# leo_RPI_BUCK.net
KiCad netlist of a schematic drawn in Altium Designer
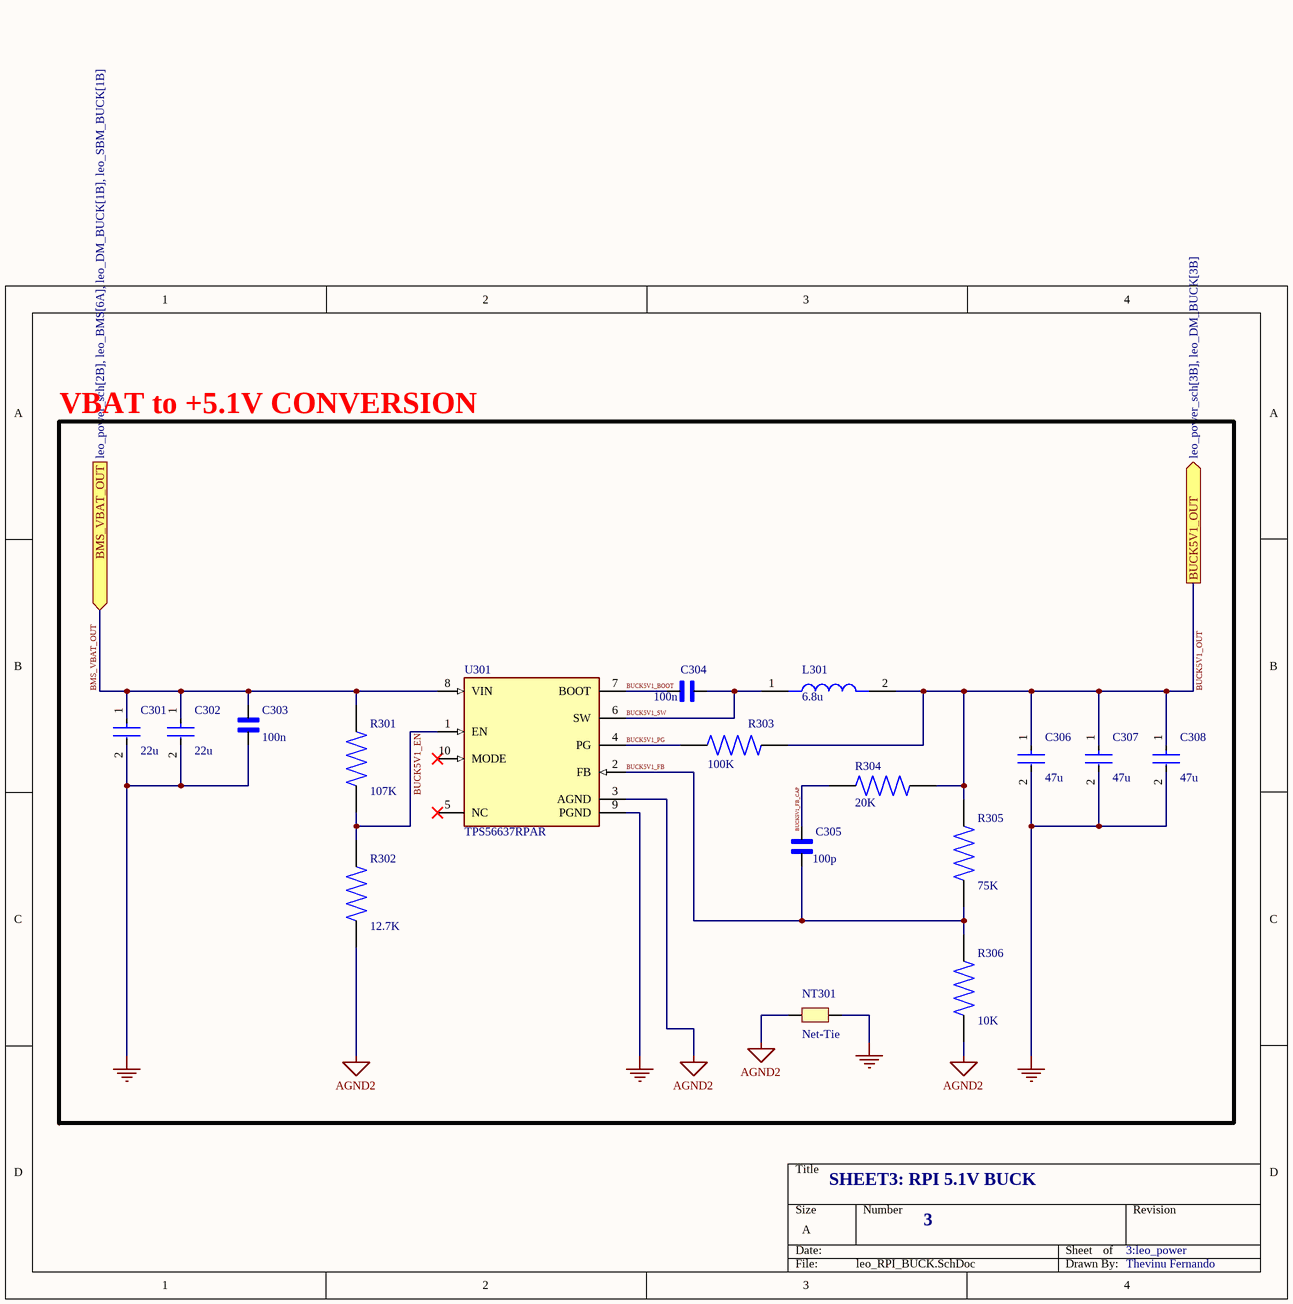
[diagram p0: leo_RPI_BUCK.SchDoc]

(export (version "E")
  (design (tool "Eeschema 10.0.6"))
  (components
    (comp (ref "C301")
      (value "22u")
      (footprint "CAP_1206")
      (fields
        (field (name "MOUSER PART NUMBER") "187-CL31A226KAHNNNE")
        (field (name "PART NUMBER") "CL31A226KAHNNNE")
        (field (name "DIGIKEY PART NUMBER") "1276-3047-1-ND")
      )
      (libsource (lib "leo_power_schlib") (part "CAP_1206"))
    )
    (comp (ref "C302")
      (value "22u")
      (footprint "CAP_1206")
      (fields
        (field (name "MOUSER PART NUMBER") "187-CL31A226KAHNNNE")
        (field (name "PART NUMBER") "CL31A226KAHNNNE")
        (field (name "DIGIKEY PART NUMBER") "1276-3047-1-ND")
      )
      (libsource (lib "leo_power_schlib") (part "CAP_1206"))
    )
    (comp (ref "C303")
      (value "100n")
      (footprint "CAP_0603")
      (description "Â±10% 50V Ceramic Capacitor X7R 0603 (1608 Metric)")
      (fields (field (name "MF") "Samsung Electro-Mechanics") (field (name "MP") "CL10B104KB8NNNC"))
      (libsource (lib "leo_power_schlib") (part "CAP_0603"))
    )
    (comp (ref "C304")
      (value "100n")
      (footprint "CAP_0402")
      (description "±10% 50V Ceramic Capacitor X7R 0402")
      (fields (field (name "MF") "Samsung") (field (name "MP") "CL05B104KO5NNNC"))
      (libsource (lib "leo_power_schlib") (part "CAP_0402"))
    )
    (comp (ref "C305")
      (value "100p")
      (footprint "CAP_0402")
      (description "±10% 50V Ceramic Capacitor X7R 0402")
      (fields (field (name "MF") "Samsung") (field (name "MP") "CL05B104KO5NNNC"))
      (libsource (lib "") (part "CAP_0402_1"))
    )
    (comp (ref "C306")
      (value "47u")
      (footprint "CAP_1206")
      (fields
        (field (name "MOUSER PART NUMBER") "187-CL31A226KAHNNNE")
        (field (name "PART NUMBER") "CL31A226KAHNNNE")
        (field (name "DIGIKEY PART NUMBER") "1276-3047-1-ND")
      )
      (libsource (lib "leo_power_schlib") (part "CAP_1206"))
    )
    (comp (ref "C307")
      (value "47u")
      (footprint "CAP_1206")
      (fields
        (field (name "MOUSER PART NUMBER") "187-CL31A226KAHNNNE")
        (field (name "PART NUMBER") "CL31A226KAHNNNE")
        (field (name "DIGIKEY PART NUMBER") "1276-3047-1-ND")
      )
      (libsource (lib "leo_power_schlib") (part "CAP_1206"))
    )
    (comp (ref "C308")
      (value "47u")
      (footprint "CAP_1206")
      (fields
        (field (name "MOUSER PART NUMBER") "187-CL31A226KAHNNNE")
        (field (name "PART NUMBER") "CL31A226KAHNNNE")
        (field (name "DIGIKEY PART NUMBER") "1276-3047-1-ND")
      )
      (libsource (lib "leo_power_schlib") (part "CAP_1206"))
    )
    (comp (ref "L301")
      (value "6.8u")
      (footprint "IND_104CDMCCDS-8R2MC")
      (description "Inductor Power Shielded/Molded Wirewound 8.2uH 20% 100KHz Metal 8.3A 0.027Ohm DCR 4040 T/R")
      (fields (field (name "MF") "Sumida") (field (name "MP") "104CDMCCDS-8R2MC"))
      (libsource (lib "leo_power_schlib") (part "104CDMCCDS-8R2MC"))
    )
    (comp (ref "NT301")
      (value "Net-Tie")
      (footprint "NET-TIE_SMD")
      (description "Single point connection between nets.")
      (libsource (lib "leo_power_schlib") (part "NET-TIE"))
    )
    (comp (ref "R301")
      (value "107K")
      (footprint "RES_0603")
      (description "Â±1% 0.1W, 1/10W Chip Resistor 0603 (1608 Metric) Moisture Resistant Thick Film")
      (fields (field (name "MF") "Yageo") (field (name "MP") "RC0603FR-0791KL"))
      (libsource (lib "leo_power_schlib") (part "RES_0603"))
    )
    (comp (ref "R302")
      (value "12.7K")
      (footprint "RES_0603")
      (description "Â±1% 0.1W, 1/10W Chip Resistor 0603 (1608 Metric) Moisture Resistant Thick Film")
      (fields (field (name "MF") "Yageo") (field (name "MP") "RC0603FR-0791KL"))
      (libsource (lib "leo_power_schlib") (part "RES_0603"))
    )
    (comp (ref "R303")
      (value "100K")
      (footprint "RES_0402")
      (description "Chip Resistor 0402 (1005 Metric) Automotive AEC-Q200 Thick Film")
      (fields (field (name "MF") "Panasonic") (field (name "MP") "ERJ-2RKF1002X"))
      (libsource (lib "leo_power_schlib") (part "RES_0402"))
    )
    (comp (ref "R304")
      (value "20K")
      (footprint "RES_0402")
      (description "Chip Resistor 0402 (1005 Metric) Automotive AEC-Q200 Thick Film")
      (fields (field (name "MF") "Panasonic") (field (name "MP") "ERJ-2RKF1002X"))
      (libsource (lib "leo_power_schlib") (part "RES_0402"))
    )
    (comp (ref "R305")
      (value "75K")
      (footprint "RES_0603")
      (description "Â±1% 0.1W, 1/10W Chip Resistor 0603 (1608 Metric) Moisture Resistant Thick Film")
      (fields (field (name "MF") "Yageo") (field (name "MP") "RC0603FR-0791KL"))
      (libsource (lib "leo_power_schlib") (part "RES_0603"))
    )
    (comp (ref "R306")
      (value "10K")
      (footprint "RES_0603")
      (description "Â±1% 0.1W, 1/10W Chip Resistor 0603 (1608 Metric) Moisture Resistant Thick Film")
      (fields (field (name "MF") "Yageo") (field (name "MP") "RC0603FR-0791KL"))
      (libsource (lib "leo_power_schlib") (part "RES_0603"))
    )
    (comp (ref "U301")
      (value "TPS56637RPAR")
      (footprint "FP-RPA0010A-MFG")
      (description "Buck Switching Regulator IC Adjustable 0.6V~13V 1 Output 6A VQFN-10-HR(3x3)")
      (fields
        (field (name "OCTOPART") "https://octopart.com/tps56637rpar-texas+instruments-97650653")
        (field (name "MANUFACTURER") "Texas Instruments")
      )
      (libsource (lib "leo_power_schlib") (part "TPS56637RPAR"))
    )
  )
  (nets
    (net (code "1") (name "/BMS_VBAT_OUT") (class "Default")
      (node (ref "C301") (pin "1") (pinfunction "1_1") (pintype "passive"))
      (node (ref "C302") (pin "1") (pinfunction "1_1") (pintype "passive"))
      (node (ref "C303") (pin "2") (pinfunction "2_2") (pintype "passive"))
      (node (ref "R301") (pin "2") (pinfunction "2_2") (pintype "passive"))
      (node (ref "U301") (pin "8") (pinfunction "VIN_8") (pintype "input"))
    )
    (net (code "2") (name "/BUCK5V1_BOOT") (class "Default")
      (node (ref "C304") (pin "1") (pinfunction "1_1") (pintype "passive"))
      (node (ref "U301") (pin "7") (pinfunction "BOOT_7") (pintype "power_in"))
    )
    (net (code "3") (name "/BUCK5V1_EN") (class "Default")
      (node (ref "R301") (pin "1") (pinfunction "1_1") (pintype "passive"))
      (node (ref "R302") (pin "2") (pinfunction "2_2") (pintype "passive"))
      (node (ref "U301") (pin "1") (pinfunction "EN_1") (pintype "input"))
    )
    (net (code "4") (name "/BUCK5V1_FB") (class "Default")
      (node (ref "C305") (pin "1") (pinfunction "1_1") (pintype "passive"))
      (node (ref "R305") (pin "1") (pinfunction "1_1") (pintype "passive"))
      (node (ref "R306") (pin "2") (pinfunction "2_2") (pintype "passive"))
      (node (ref "U301") (pin "2") (pinfunction "FB_2") (pintype "input"))
    )
    (net (code "5") (name "/BUCK5V1_FB_CAP") (class "Default")
      (node (ref "C305") (pin "2") (pinfunction "2_2") (pintype "passive"))
      (node (ref "R304") (pin "1") (pinfunction "1_1") (pintype "passive"))
    )
    (net (code "6") (name "/BUCK5V1_OUT") (class "Default")
      (node (ref "C306") (pin "1") (pinfunction "1_1") (pintype "passive"))
      (node (ref "C307") (pin "1") (pinfunction "1_1") (pintype "passive"))
      (node (ref "C308") (pin "1") (pinfunction "1_1") (pintype "passive"))
      (node (ref "L301") (pin "2") (pinfunction "2_2") (pintype "passive"))
      (node (ref "R303") (pin "2") (pinfunction "2_2") (pintype "passive"))
      (node (ref "R304") (pin "2") (pinfunction "2_2") (pintype "passive"))
      (node (ref "R305") (pin "2") (pinfunction "2_2") (pintype "passive"))
    )
    (net (code "7") (name "/BUCK5V1_PG") (class "Default")
      (node (ref "R303") (pin "1") (pinfunction "1_1") (pintype "passive"))
      (node (ref "U301") (pin "4") (pinfunction "PG_4") (pintype "open_collector"))
    )
    (net (code "8") (name "/BUCK5V1_SW") (class "Default")
      (node (ref "C304") (pin "2") (pinfunction "2_2") (pintype "passive"))
      (node (ref "L301") (pin "1") (pinfunction "1_1") (pintype "passive"))
      (node (ref "U301") (pin "6") (pinfunction "SW_6") (pintype "power_in"))
    )
    (net (code "9") (name "AGND2") (class "Default")
      (node (ref "NT301") (pin "2") (pinfunction "2_2") (pintype "passive"))
      (node (ref "R302") (pin "1") (pinfunction "1_1") (pintype "passive"))
      (node (ref "R306") (pin "1") (pinfunction "1_1") (pintype "passive"))
      (node (ref "U301") (pin "3") (pinfunction "AGND_3") (pintype "power_in"))
    )
    (net (code "10") (name "GND") (class "Default")
      (node (ref "C301") (pin "2") (pinfunction "2_2") (pintype "passive"))
      (node (ref "C302") (pin "2") (pinfunction "2_2") (pintype "passive"))
      (node (ref "C303") (pin "1") (pinfunction "1_1") (pintype "passive"))
      (node (ref "C306") (pin "2") (pinfunction "2_2") (pintype "passive"))
      (node (ref "C307") (pin "2") (pinfunction "2_2") (pintype "passive"))
      (node (ref "C308") (pin "2") (pinfunction "2_2") (pintype "passive"))
      (node (ref "NT301") (pin "1") (pinfunction "1_1") (pintype "passive"))
      (node (ref "U301") (pin "9") (pinfunction "PGND_9") (pintype "power_in"))
    )
    (net (code "11") (name "unconnected-(U301-MODE-Pad10)") (class "Default")
      (node (ref "U301") (pin "10") (pinfunction "MODE_10") (pintype "input+no_connect"))
    )
    (net (code "12") (name "unconnected-(U301-NC-Pad5)") (class "Default")
      (node (ref "U301") (pin "5") (pinfunction "NC_5") (pintype "passive+no_connect"))
    )
  )
)
